# 06_ISO_CAN.net
KiCad netlist of a schematic drawn in Altium Designer
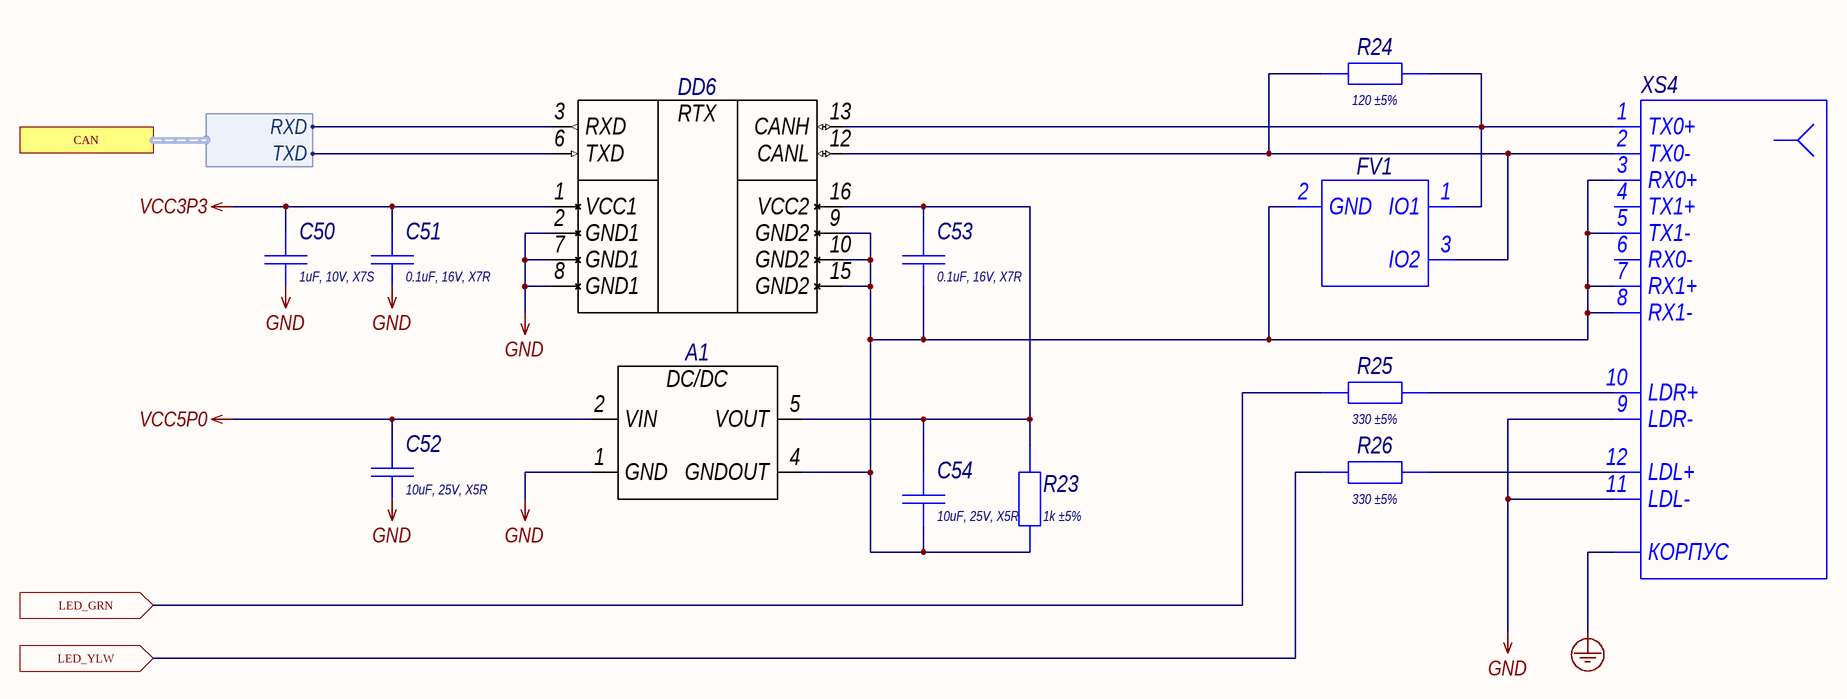
[diagram p0: 06_ISO_CAN.SchDoc]

(export (version "E")
  (design (tool "Eeschema 10.0.6"))
  (components
    (comp (ref "A1")
      (value "BxxxxXT-1WR3")
      (footprint "BxxxxXT-1WR3")
      (fields
        (field (name "PART NUMBER") "B0505XT-1WR3")
        (field (name "MANUFACTURER") "Mornsun")
        (field (name "PUBLISHER") "Andrew Danich")
      )
      (libsource (lib "ADLib") (part "BxxxxXT-1WR3"))
    )
    (comp (ref "C50")
      (value "Capacitor")
      (footprint "C0402_L")
      (fields
        (field (name "SCHEMATIC VALUE") "1uF, 10V, X7S")
        (field (name "PART NUMBER") "GRM155C71A105KE11D")
        (field (name "VOLTAGE") "10V")
        (field (name "TOLERANCE") "±10%")
        (field (name "PUBLISHER") "Andrew Danich")
      )
      (libsource (lib "ADLib") (part "Capacitor"))
    )
    (comp (ref "C51")
      (value "Capacitor")
      (footprint "C0402_L")
      (fields
        (field (name "SCHEMATIC VALUE") "0.1uF, 16V, X7R")
        (field (name "PART NUMBER") "GCM155R71C104KA55D")
        (field (name "VOLTAGE") "16V")
        (field (name "TOLERANCE") "±10%")
        (field (name "PUBLISHER") "Andrew Danich")
      )
      (libsource (lib "ADLib") (part "Capacitor"))
    )
    (comp (ref "C52")
      (value "Capacitor")
      (footprint "C0603_L")
      (fields
        (field (name "SCHEMATIC VALUE") "10uF, 25V, X5R")
        (field (name "PART NUMBER") "GRM188R61E106MA73D")
        (field (name "VOLTAGE") "25V")
        (field (name "TOLERANCE") "±20%")
        (field (name "PUBLISHER") "Andrew Danich")
      )
      (libsource (lib "ADLib") (part "Capacitor"))
    )
    (comp (ref "C53")
      (value "Capacitor")
      (footprint "C0402_L")
      (fields
        (field (name "SCHEMATIC VALUE") "0.1uF, 16V, X7R")
        (field (name "PART NUMBER") "GCM155R71C104KA55D")
        (field (name "VOLTAGE") "16V")
        (field (name "TOLERANCE") "±10%")
        (field (name "PUBLISHER") "Andrew Danich")
      )
      (libsource (lib "ADLib") (part "Capacitor"))
    )
    (comp (ref "C54")
      (value "Capacitor")
      (footprint "C0603_L")
      (fields
        (field (name "SCHEMATIC VALUE") "10uF, 25V, X5R")
        (field (name "PART NUMBER") "GRM188R61E106MA73D")
        (field (name "VOLTAGE") "25V")
        (field (name "TOLERANCE") "±20%")
        (field (name "PUBLISHER") "Andrew Danich")
      )
      (libsource (lib "ADLib") (part "Capacitor"))
    )
    (comp (ref "DD6")
      (value "ISO1050DW")
      (footprint "SOIC-16_127P1030X750X265_N")
      (fields
        (field (name "PART NUMBER") "ISO1050DWR")
        (field (name "MANUFACTURER") "Texas Instruments")
        (field (name "PUBLISHER") "Andrew Danich")
      )
      (libsource (lib "ADLib") (part "ISO1050DW"))
    )
    (comp (ref "FV1")
      (value "ESDCANxx-2BLY-Series")
      (footprint "SOT-23_190P290X160X145_N")
      (fields
        (field (name "PART NUMBER") "ESDCAN24-2BLY")
        (field (name "MANUFACTURER") "STMicroelectronics")
        (field (name "PUBLISHER") "Andrew Danich")
      )
      (libsource (lib "ADLib") (part "ESDCANxx-2BLY-Series"))
    )
    (comp (ref "R23")
      (value "Resistor")
      (footprint "R0603_L")
      (fields
        (field (name "SCHEMATIC VALUE") "1k ±5%")
        (field (name "PART NUMBER") "RC0603JR-071KL")
        (field (name "TOLERANCE") "±5%")
        (field (name "MANUFACTURER") "Yageo")
        (field (name "PUBLISHER") "Andrew Danich")
      )
      (libsource (lib "ADLib") (part "Resistor"))
    )
    (comp (ref "R24")
      (value "Resistor")
      (footprint "R0805_L")
      (fields
        (field (name "SCHEMATIC VALUE") "120 ±5%")
        (field (name "PART NUMBER") "RC0805JR-07120RL")
        (field (name "TOLERANCE") "±5%")
        (field (name "MANUFACTURER") "Yageo")
        (field (name "PUBLISHER") "Andrew Danich")
      )
      (libsource (lib "ADLib") (part "Resistor"))
    )
    (comp (ref "R25")
      (value "Resistor")
      (footprint "R0402_L")
      (fields
        (field (name "SCHEMATIC VALUE") "330 ±5%")
        (field (name "PART NUMBER") "RC0402JR-07330RL")
        (field (name "TOLERANCE") "±5%")
        (field (name "MANUFACTURER") "Yageo")
        (field (name "PUBLISHER") "Andrew Danich")
      )
      (libsource (lib "ADLib") (part "Resistor"))
    )
    (comp (ref "R26")
      (value "Resistor")
      (footprint "R0402_L")
      (fields
        (field (name "SCHEMATIC VALUE") "330 ±5%")
        (field (name "PART NUMBER") "RC0402JR-07330RL")
        (field (name "TOLERANCE") "±5%")
        (field (name "MANUFACTURER") "Yageo")
        (field (name "PUBLISHER") "Andrew Danich")
      )
      (libsource (lib "ADLib") (part "Resistor"))
    )
    (comp (ref "XS4")
      (value "CAN")
      (footprint "615008137421")
      (fields
        (field (name "PART NUMBER") "615008137421")
        (field (name "MANUFACTURER") "Wurth Elektronik")
        (field (name "PUBLISHER") "Andrew Danich")
      )
      (libsource (lib "ADLib") (part "615008137421"))
    )
  )
  (nets
    (net (code "2") (name "/LED_GRN") (class "Default")
      (node (ref "R25") (pin "1") (pinfunction "1_1") (pintype "passive"))
    )
    (net (code "3") (name "/LED_YLW") (class "Default")
      (node (ref "R26") (pin "1") (pinfunction "1_1") (pintype "passive"))
    )
    (net (code "4") (name "/RXD") (class "Default")
      (node (ref "DD6") (pin "3") (pinfunction "RXD_3") (pintype "output"))
    )
    (net (code "5") (name "/TXD") (class "Default")
      (node (ref "DD6") (pin "6") (pinfunction "TXD_6") (pintype "input"))
    )
    (net (code "7") (name "EARTH") (class "Default")
      (node (ref "XS4") (pin "SH") (pinfunction "КОРПУС_SH") (pintype "passive"))
    )
    (net (code "8") (name "GND") (class "Default")
      (node (ref "A1") (pin "1") (pinfunction "GND_1") (pintype "power_in"))
      (node (ref "C50") (pin "1") (pinfunction "1_1") (pintype "passive"))
      (node (ref "C51") (pin "1") (pinfunction "1_1") (pintype "passive"))
      (node (ref "C52") (pin "1") (pinfunction "1_1") (pintype "passive"))
      (node (ref "DD6") (pin "2") (pinfunction "GND1_2") (pintype "power_in"))
      (node (ref "DD6") (pin "7") (pinfunction "GND1_7") (pintype "power_in"))
      (node (ref "DD6") (pin "8") (pinfunction "GND1_8") (pintype "power_in"))
      (node (ref "XS4") (pin "11") (pinfunction "LDL-_11") (pintype "passive"))
      (node (ref "XS4") (pin "9") (pinfunction "LDR-_9") (pintype "passive"))
    )
    (net (code "9") (name "Net-(A1-GNDOUT)") (class "Default")
      (node (ref "A1") (pin "4") (pinfunction "GNDOUT_4") (pintype "power_in"))
      (node (ref "C53") (pin "1") (pinfunction "1_1") (pintype "passive"))
      (node (ref "C54") (pin "1") (pinfunction "1_1") (pintype "passive"))
      (node (ref "DD6") (pin "10") (pinfunction "GND2_10") (pintype "power_in"))
      (node (ref "DD6") (pin "15") (pinfunction "GND2_15") (pintype "power_in"))
      (node (ref "DD6") (pin "9") (pinfunction "GND2_9") (pintype "power_in"))
      (node (ref "FV1") (pin "2") (pinfunction "GND_2") (pintype "passive"))
      (node (ref "R23") (pin "1") (pinfunction "1_1") (pintype "passive"))
      (node (ref "XS4") (pin "3") (pinfunction "RX0+_3") (pintype "passive"))
      (node (ref "XS4") (pin "5") (pinfunction "TX1-_5") (pintype "passive"))
      (node (ref "XS4") (pin "7") (pinfunction "RX1+_7") (pintype "passive"))
      (node (ref "XS4") (pin "8") (pinfunction "RX1-_8") (pintype "passive"))
    )
    (net (code "10") (name "Net-(A1-VOUT)") (class "Default")
      (node (ref "A1") (pin "5") (pinfunction "VOUT_5") (pintype "power_in"))
      (node (ref "C53") (pin "2") (pinfunction "2_2") (pintype "passive"))
      (node (ref "C54") (pin "2") (pinfunction "2_2") (pintype "passive"))
      (node (ref "DD6") (pin "16") (pinfunction "VCC2_16") (pintype "power_in"))
      (node (ref "R23") (pin "2") (pinfunction "2_2") (pintype "passive"))
    )
    (net (code "11") (name "Net-(DD6-CANH)") (class "Default")
      (node (ref "DD6") (pin "13") (pinfunction "CANH_13") (pintype "bidirectional"))
      (node (ref "FV1") (pin "1") (pinfunction "IO1_1") (pintype "passive"))
      (node (ref "R24") (pin "2") (pinfunction "2_2") (pintype "passive"))
      (node (ref "XS4") (pin "1") (pinfunction "TX0+_1") (pintype "passive"))
    )
    (net (code "12") (name "Net-(DD6-CANL)") (class "Default")
      (node (ref "DD6") (pin "12") (pinfunction "CANL_12") (pintype "bidirectional"))
      (node (ref "FV1") (pin "3") (pinfunction "IO2_3") (pintype "passive"))
      (node (ref "R24") (pin "1") (pinfunction "1_1") (pintype "passive"))
      (node (ref "XS4") (pin "2") (pinfunction "TX0-_2") (pintype "passive"))
    )
    (net (code "13") (name "Net-(XS4-LDL+)") (class "Default")
      (node (ref "R26") (pin "2") (pinfunction "2_2") (pintype "passive"))
      (node (ref "XS4") (pin "12") (pinfunction "LDL+_12") (pintype "passive"))
    )
    (net (code "14") (name "Net-(XS4-LDR+)") (class "Default")
      (node (ref "R25") (pin "2") (pinfunction "2_2") (pintype "passive"))
      (node (ref "XS4") (pin "10") (pinfunction "LDR+_10") (pintype "passive"))
    )
    (net (code "15") (name "VCC3P3") (class "Default")
      (node (ref "C50") (pin "2") (pinfunction "2_2") (pintype "passive"))
      (node (ref "C51") (pin "2") (pinfunction "2_2") (pintype "passive"))
      (node (ref "DD6") (pin "1") (pinfunction "VCC1_1") (pintype "power_in"))
    )
    (net (code "16") (name "VCC5P0") (class "Default")
      (node (ref "A1") (pin "2") (pinfunction "VIN_2") (pintype "power_in"))
      (node (ref "C52") (pin "2") (pinfunction "2_2") (pintype "passive"))
    )
    (net (code "17") (name "unconnected-(XS4-RX0--Pad6)") (class "Default")
      (node (ref "XS4") (pin "6") (pinfunction "RX0-_6") (pintype "passive"))
    )
    (net (code "18") (name "unconnected-(XS4-TX1+-Pad4)") (class "Default")
      (node (ref "XS4") (pin "4") (pinfunction "TX1+_4") (pintype "passive"))
    )
  )
)
